# STM32_microcontroller_power.net
KiCad netlist of a schematic drawn in Altium Designer
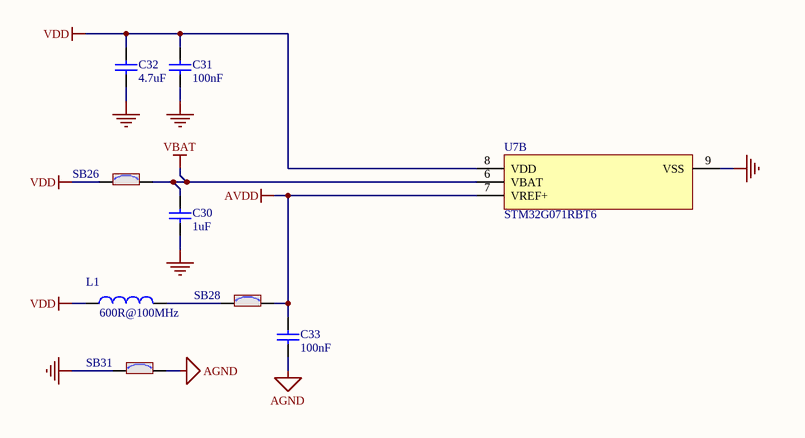
[diagram p0: STM32_microcontroller_power.SchDoc]

(export (version "E")
  (design (tool "Eeschema 10.0.6"))
  (components
    (comp (ref "C30")
      (value "1uF")
      (footprint "C0603")
      (description "Capacitor, MLCC, 1uF, 16V, X5R, 10%, 0603, T=0,8mm")
      (fields
        (field (name "INTERNAL_PART_NUMBER") "MCD-00010")
        (field (name "MANUFACTURER_PART_NUMBER") "CC0603KRX5R7BB105")
        (field (name "PROVIDED_BY") "SUBCO")
      )
      (libsource (lib "MCD_PARTS_database") (part "Capacitor"))
    )
    (comp (ref "C31")
      (value "100nF")
      (footprint "C0603")
      (description "Capacitor, MLCC, 100nF, 16V, X7R, 10%, 0603, T=0,8mm")
      (fields
        (field (name "INTERNAL_PART_NUMBER") "MCD-00211")
        (field (name "MANUFACTURER_PART_NUMBER") "CC0603KRX7R7BB104")
        (field (name "PROVIDED_BY") "SUBCO")
      )
      (libsource (lib "MCD_PARTS_database") (part "Capacitor"))
    )
    (comp (ref "C32")
      (value "4.7uF")
      (footprint "C0603")
      (description "Capacitor, MLCC, 4.7uF, 16V, X5R, 10%, 0603, T=0.8mm")
      (fields
        (field (name "INTERNAL_PART_NUMBER") "MCD-00009")
        (field (name "MANUFACTURER_PART_NUMBER") "CC0603KRX5R7BB475")
        (field (name "PROVIDED_BY") "SUBCO")
      )
      (libsource (lib "MCD_PARTS_database") (part "Capacitor"))
    )
    (comp (ref "C33")
      (value "100nF")
      (footprint "C0603")
      (description "Capacitor, MLCC, 100nF, 16V, X7R, 10%, 0603, T=0,8mm")
      (fields
        (field (name "INTERNAL_PART_NUMBER") "MCD-00211")
        (field (name "MANUFACTURER_PART_NUMBER") "CC0603KRX7R7BB104")
        (field (name "PROVIDED_BY") "SUBCO")
      )
      (libsource (lib "MCD_PARTS_database") (part "Capacitor"))
    )
    (comp (ref "L1")
      (value "600R@100MHz")
      (footprint "L0603")
      (description "SMD Chip ferrite bead, 600R@100MHz +/-25%, 350mA, 500mohm DC, 0603, T=0.8mm")
      (fields
        (field (name "INTERNAL_PART_NUMBER") "MCD-00047")
        (field (name "MANUFACTURER_PART_NUMBER") "FCM1608KF-601T03")
        (field (name "PROVIDED_BY") "SUBCO")
      )
      (libsource (lib "MCD_PARTS_database") (part "BEAD"))
    )
    (comp (ref "SB26")
      (value "SB_ON")
      (footprint "SOLDER-BRIDGE_R0603-0R")
      (description "Solder Bridge ON")
      (fields
        (field (name "INTERNAL_PART_NUMBER") "MCD-00071")
        (field (name "MANUFACTURER_PART_NUMBER") "RC0603JR-070RL")
        (field (name "PROVIDED_BY") "SUBCO")
      )
      (libsource (lib "MCD_PARTS_database") (part "SB_ON"))
    )
    (comp (ref "SB28")
      (value "SB_ON")
      (footprint "SOLDER-BRIDGE_R0603-0R")
      (description "Solder Bridge ON")
      (fields
        (field (name "INTERNAL_PART_NUMBER") "MCD-00071")
        (field (name "MANUFACTURER_PART_NUMBER") "RC0603JR-070RL")
        (field (name "PROVIDED_BY") "SUBCO")
      )
      (libsource (lib "MCD_PARTS_database") (part "SB_ON"))
    )
    (comp (ref "SB31")
      (value "SB_ON")
      (footprint "SOLDER-BRIDGE_R0603-0R")
      (description "Solder Bridge ON")
      (fields
        (field (name "INTERNAL_PART_NUMBER") "MCD-00071")
        (field (name "MANUFACTURER_PART_NUMBER") "RC0603JR-070RL")
        (field (name "PROVIDED_BY") "SUBCO")
      )
      (libsource (lib "MCD_PARTS_database") (part "SB_ON"))
    )
    (comp (ref "U7")
      (value "STM32G071RBT6")
      (footprint "ICC_LQFP64_10X10_P050_SOCKET_YAMAICHI_IC149-064-069-B5")
      (fields
        (field (name "INTERNAL_PART_NUMBER") "MCD-00662")
        (field (name "MANUFACTURER") "STMICROELECTRONICS")
        (field (name "BMS_PART_NUMBER") "9175318")
        (field (name "PROVIDED_BY") "SUBCO with ST control")
      )
      (libsource (lib "MCD_PARTS_database") (part "STM32G071RBT6"))
    )
  )
  (nets
    (net (code "1") (name "AGND") (class "Default")
      (node (ref "C33") (pin "1") (pinfunction "1_1") (pintype "passive"))
      (node (ref "SB31") (pin "2") (pinfunction "2_2") (pintype "passive"))
    )
    (net (code "2") (name "AVDD") (class "Default")
      (node (ref "C33") (pin "2") (pinfunction "2_2") (pintype "passive"))
      (node (ref "SB28") (pin "2") (pinfunction "2_2") (pintype "passive"))
      (node (ref "U7") (pin "7") (pinfunction "VREF+_7") (pintype "power_in"))
    )
    (net (code "3") (name "GND") (class "Default")
      (node (ref "C30") (pin "1") (pinfunction "1_1") (pintype "passive"))
      (node (ref "C31") (pin "1") (pinfunction "1_1") (pintype "passive"))
      (node (ref "C32") (pin "1") (pinfunction "1_1") (pintype "passive"))
      (node (ref "SB31") (pin "1") (pinfunction "1_1") (pintype "passive"))
      (node (ref "U7") (pin "9") (pinfunction "VSS_9") (pintype "passive"))
    )
    (net (code "4") (name "Net-(L1-Pad2)") (class "Default")
      (node (ref "L1") (pin "2") (pinfunction "2_2") (pintype "passive"))
      (node (ref "SB28") (pin "1") (pinfunction "1_1") (pintype "passive"))
    )
    (net (code "5") (name "VBAT") (class "Default")
      (node (ref "C30") (pin "2") (pinfunction "2_2") (pintype "passive"))
      (node (ref "SB26") (pin "2") (pinfunction "2_2") (pintype "passive"))
      (node (ref "U7") (pin "6") (pinfunction "VBAT_6") (pintype "power_in"))
    )
    (net (code "6") (name "VDD") (class "Default")
      (node (ref "C31") (pin "2") (pinfunction "2_2") (pintype "passive"))
      (node (ref "C32") (pin "2") (pinfunction "2_2") (pintype "passive"))
      (node (ref "L1") (pin "1") (pinfunction "1_1") (pintype "passive"))
      (node (ref "SB26") (pin "1") (pinfunction "1_1") (pintype "passive"))
      (node (ref "U7") (pin "8") (pinfunction "VDD_8") (pintype "power_in"))
    )
  )
)
